# ll_target.net
KiCad netlist of a schematic drawn in EAGLE
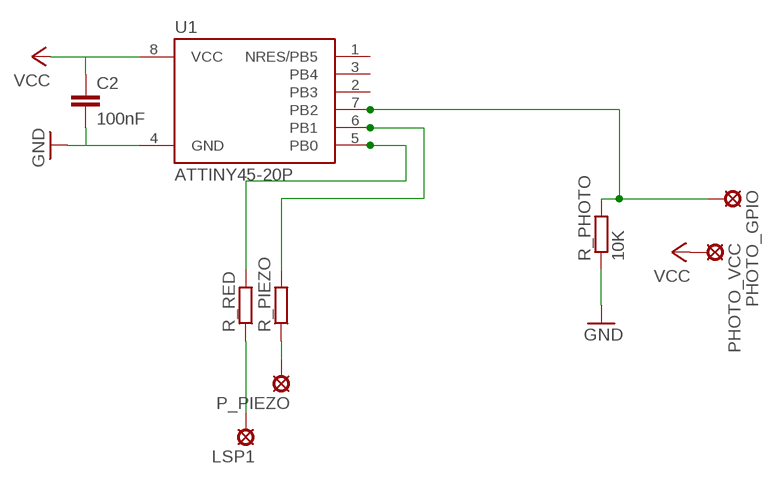
[diagram p0: schematic, sheet 1]

(export (version "E")
  (design (tool "Eeschema 10.0.6"))
  (components
    (comp (ref "C2")
      (value "100nF")
      (footprint "eagle-import:C025-025X050")
      (libsource (lib "eagle-import") (part "C-EU025-025X050"))
    )
    (comp (ref "LSP1")
      (value "LSP10")
      (footprint "eagle-import:LSP10")
      (libsource (lib "eagle-import") (part "LSP10"))
    )
    (comp (ref "PHOTO_GPIO")
      (value "LSP10")
      (footprint "eagle-import:LSP10")
      (libsource (lib "eagle-import") (part "LSP10"))
    )
    (comp (ref "PHOTO_VCC")
      (value "LSP10")
      (footprint "eagle-import:LSP10")
      (libsource (lib "eagle-import") (part "LSP10"))
    )
    (comp (ref "P_PIEZO")
      (value "LSP10")
      (footprint "eagle-import:LSP10")
      (libsource (lib "eagle-import") (part "LSP10"))
    )
    (comp (ref "R_PHOTO")
      (value "10K")
      (footprint "eagle-import:0204_7")
      (libsource (lib "eagle-import") (part "R-EU_0204/7"))
    )
    (comp (ref "R_PIEZO")
      (value "R-EU_0204/7")
      (footprint "eagle-import:0204_7")
      (libsource (lib "eagle-import") (part "R-EU_0204/7"))
    )
    (comp (ref "R_RED")
      (value "R-EU_0204/7")
      (footprint "eagle-import:0204_7")
      (libsource (lib "eagle-import") (part "R-EU_0204/7"))
    )
    (comp (ref "U1")
      (value "ATTINY45-20P")
      (footprint "eagle-import:PDIP08_300MIL")
      (libsource (lib "eagle-import") (part "ATTINY45P-20"))
    )
  )
  (nets
    (net (code "1") (name "GND") (class "Default")
      (node (ref "C2") (pin "2") (pinfunction "2_2") (pintype "passive"))
      (node (ref "R_PHOTO") (pin "1") (pinfunction "1_1") (pintype "passive"))
      (node (ref "U1") (pin "4") (pinfunction "GND_4") (pintype "power_in"))
    )
    (net (code "2") (name "Net-(LSP1-PadMP)") (class "Default")
      (node (ref "LSP1") (pin "MP") (pinfunction "MP_MP") (pintype "passive"))
      (node (ref "R_RED") (pin "1") (pinfunction "1_1") (pintype "passive"))
    )
    (net (code "3") (name "Net-(P_PIEZO-PadMP)") (class "Default")
      (node (ref "P_PIEZO") (pin "MP") (pinfunction "MP_MP") (pintype "passive"))
      (node (ref "R_PIEZO") (pin "1") (pinfunction "1_1") (pintype "passive"))
    )
    (net (code "4") (name "Net-(U1-PB0)") (class "Default")
      (node (ref "R_RED") (pin "2") (pinfunction "2_2") (pintype "passive"))
      (node (ref "U1") (pin "5") (pinfunction "PB0_5") (pintype "bidirectional"))
    )
    (net (code "5") (name "Net-(U1-PB1)") (class "Default")
      (node (ref "R_PIEZO") (pin "2") (pinfunction "2_2") (pintype "passive"))
      (node (ref "U1") (pin "6") (pinfunction "PB1_6") (pintype "bidirectional"))
    )
    (net (code "6") (name "Net-(U1-PB2)") (class "Default")
      (node (ref "PHOTO_GPIO") (pin "MP") (pinfunction "MP_MP") (pintype "passive"))
      (node (ref "R_PHOTO") (pin "2") (pinfunction "2_2") (pintype "passive"))
      (node (ref "U1") (pin "7") (pinfunction "PB2_7") (pintype "bidirectional"))
    )
    (net (code "7") (name "VCC") (class "Default")
      (node (ref "C2") (pin "1") (pinfunction "1_1") (pintype "passive"))
      (node (ref "PHOTO_VCC") (pin "MP") (pinfunction "MP_MP") (pintype "passive"))
      (node (ref "U1") (pin "8") (pinfunction "VCC_8") (pintype "power_in"))
    )
    (net (code "8") (name "unconnected-(U1-NRES{slash}PB5-Pad1)") (class "Default")
      (node (ref "U1") (pin "1") (pinfunction "NRES/PB5_1") (pintype "bidirectional"))
    )
    (net (code "9") (name "unconnected-(U1-PB3-Pad2)") (class "Default")
      (node (ref "U1") (pin "2") (pinfunction "PB3_2") (pintype "bidirectional"))
    )
    (net (code "10") (name "unconnected-(U1-PB4-Pad3)") (class "Default")
      (node (ref "U1") (pin "3") (pinfunction "PB4_3") (pintype "bidirectional"))
    )
  )
)
